# Main.net
KiCad netlist of a schematic drawn in Altium Designer
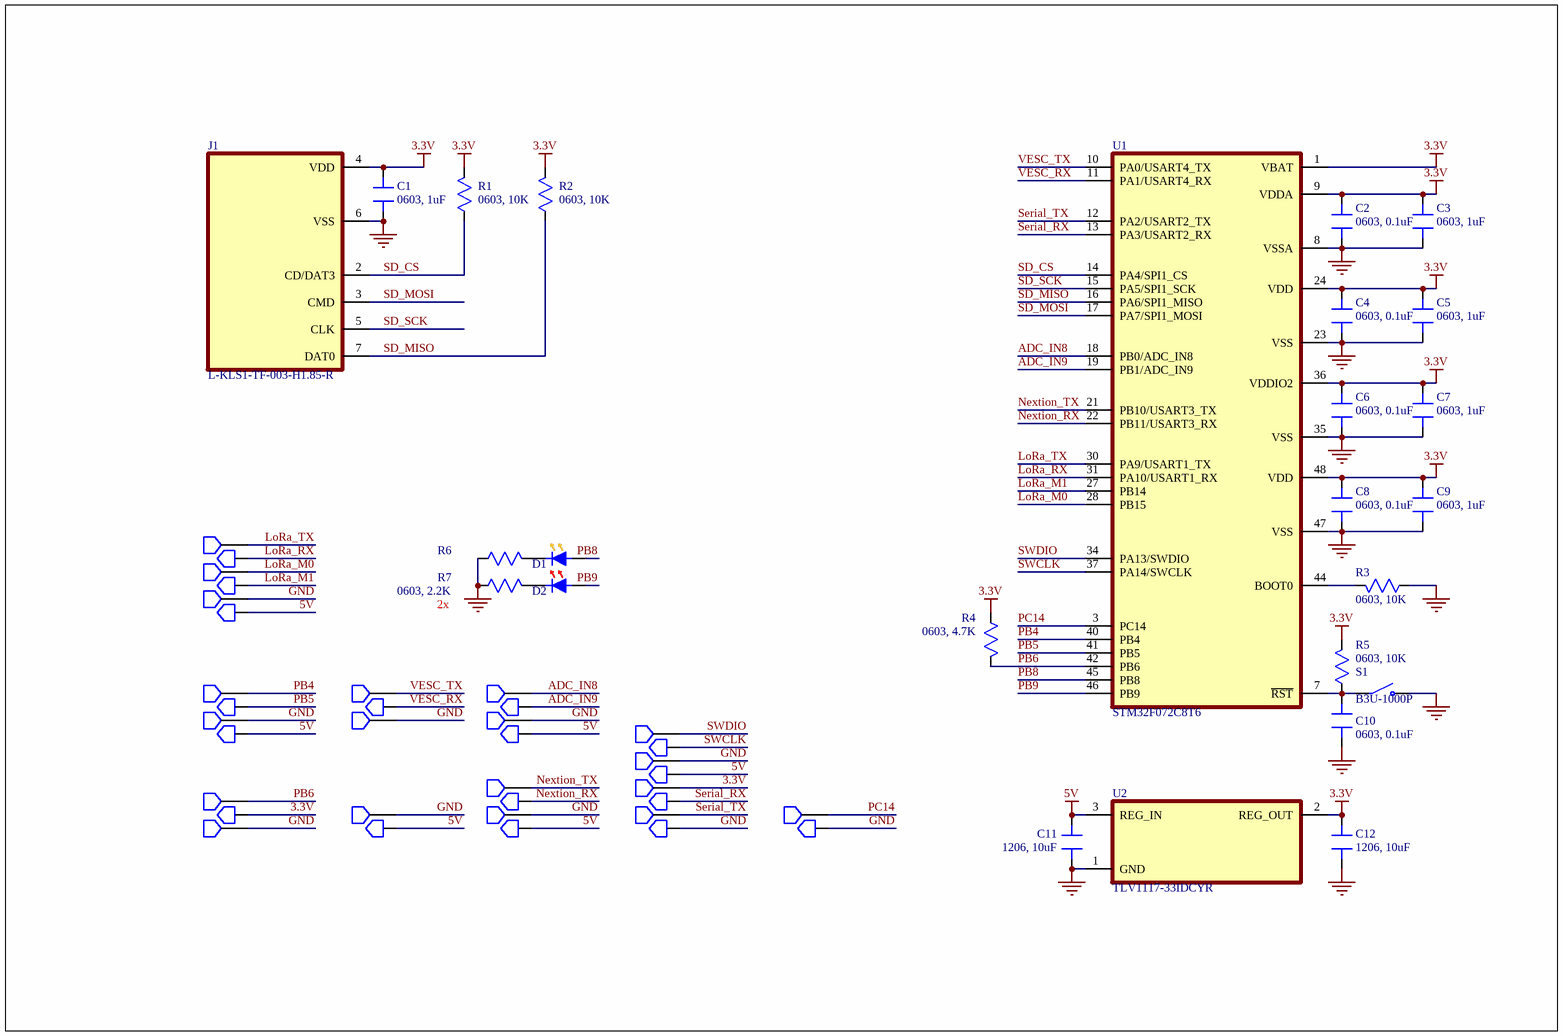
[diagram p0: Main.SchDoc]

(export (version "E")
  (design (tool "Eeschema 10.0.6"))
  (components
    (comp (ref "C1")
      (value "0603, 1uF")
      (footprint "CAP 0603_1608")
      (libsource (lib "Passives") (part "0603 Kapasitör"))
    )
    (comp (ref "C2")
      (value "0603, 0.1uF")
      (footprint "CAP 0603_1608")
      (libsource (lib "Passives") (part "0603 Kapasitör"))
    )
    (comp (ref "C3")
      (value "0603, 1uF")
      (footprint "CAP 0603_1608")
      (libsource (lib "Passives") (part "0603 Kapasitör"))
    )
    (comp (ref "C4")
      (value "0603, 0.1uF")
      (footprint "CAP 0603_1608")
      (libsource (lib "Passives") (part "0603 Kapasitör"))
    )
    (comp (ref "C5")
      (value "0603, 1uF")
      (footprint "CAP 0603_1608")
      (libsource (lib "Passives") (part "0603 Kapasitör"))
    )
    (comp (ref "C6")
      (value "0603, 0.1uF")
      (footprint "CAP 0603_1608")
      (libsource (lib "Passives") (part "0603 Kapasitör"))
    )
    (comp (ref "C7")
      (value "0603, 1uF")
      (footprint "CAP 0603_1608")
      (libsource (lib "Passives") (part "0603 Kapasitör"))
    )
    (comp (ref "C8")
      (value "0603, 0.1uF")
      (footprint "CAP 0603_1608")
      (libsource (lib "Passives") (part "0603 Kapasitör"))
    )
    (comp (ref "C9")
      (value "0603, 1uF")
      (footprint "CAP 0603_1608")
      (libsource (lib "Passives") (part "0603 Kapasitör"))
    )
    (comp (ref "C10")
      (value "0603, 0.1uF")
      (footprint "CAP 0603_1608")
      (libsource (lib "Passives") (part "0603 Kapasitör"))
    )
    (comp (ref "C11")
      (value "1206, 10uF")
      (footprint "CAP 1206_3216")
      (libsource (lib "Passives") (part "1206 Kapasitör"))
    )
    (comp (ref "C12")
      (value "1206, 10uF")
      (footprint "CAP 1206_3216")
      (libsource (lib "Passives") (part "1206 Kapasitör"))
    )
    (comp (ref "D1")
      (value "0805 LED Yellow")
      (footprint "LED 0805_2012 YELLOW")
      (libsource (lib "Passives") (part "0805 LED Yellow"))
    )
    (comp (ref "D2")
      (value "0805 LED Red")
      (footprint "LED 0805_2012 RED")
      (libsource (lib "Passives") (part "0805 LED Red"))
    )
    (comp (ref "J1")
      (value "L-KLS1-TF-003-H1.85-R")
      (footprint "L-KLS1-TF-003-H1.85-R")
      (libsource (lib "L-KLS1-TF-003-H1.85-R") (part "L-KLS1-TF-003-H1.85-R"))
    )
    (comp (ref "P1") (value "Pad1") (footprint "PAD") (libsource (lib "Passives") (part "Pad1")))
    (comp (ref "P2") (value "Pad0") (footprint "PAD") (libsource (lib "Passives") (part "Pad0")))
    (comp (ref "P3") (value "Pad1") (footprint "PAD") (libsource (lib "Passives") (part "Pad1")))
    (comp (ref "P4") (value "Pad0") (footprint "PAD") (libsource (lib "Passives") (part "Pad0")))
    (comp (ref "P5") (value "Pad1") (footprint "PAD") (libsource (lib "Passives") (part "Pad1")))
    (comp (ref "P6") (value "Pad0") (footprint "PAD") (libsource (lib "Passives") (part "Pad0")))
    (comp (ref "P7") (value "Pad1") (footprint "PAD") (libsource (lib "Passives") (part "Pad1")))
    (comp (ref "P8") (value "Pad1") (footprint "PAD") (libsource (lib "Passives") (part "Pad1")))
    (comp (ref "P9") (value "Pad1") (footprint "PAD") (libsource (lib "Passives") (part "Pad1")))
    (comp (ref "P10") (value "Pad0") (footprint "PAD") (libsource (lib "Passives") (part "Pad0")))
    (comp (ref "P11") (value "Pad0") (footprint "PAD") (libsource (lib "Passives") (part "Pad0")))
    (comp (ref "P12") (value "Pad0") (footprint "PAD") (libsource (lib "Passives") (part "Pad0")))
    (comp (ref "P13") (value "Pad1") (footprint "PAD") (libsource (lib "Passives") (part "Pad1")))
    (comp (ref "P14") (value "Pad1") (footprint "PAD") (libsource (lib "Passives") (part "Pad1")))
    (comp (ref "P15") (value "Pad1") (footprint "PAD") (libsource (lib "Passives") (part "Pad1")))
    (comp (ref "P16") (value "Pad0") (footprint "PAD") (libsource (lib "Passives") (part "Pad0")))
    (comp (ref "P17") (value "Pad0") (footprint "PAD") (libsource (lib "Passives") (part "Pad0")))
    (comp (ref "P18") (value "Pad1") (footprint "PAD") (libsource (lib "Passives") (part "Pad1")))
    (comp (ref "P19") (value "Pad0") (footprint "PAD") (libsource (lib "Passives") (part "Pad0")))
    (comp (ref "P20") (value "Pad1") (footprint "PAD") (libsource (lib "Passives") (part "Pad1")))
    (comp (ref "P21") (value "Pad0") (footprint "PAD") (libsource (lib "Passives") (part "Pad0")))
    (comp (ref "P22") (value "Pad1") (footprint "PAD") (libsource (lib "Passives") (part "Pad1")))
    (comp (ref "P23") (value "Pad1") (footprint "PAD") (libsource (lib "Passives") (part "Pad1")))
    (comp (ref "P24") (value "Pad1") (footprint "PAD") (libsource (lib "Passives") (part "Pad1")))
    (comp (ref "P25") (value "Pad0") (footprint "PAD") (libsource (lib "Passives") (part "Pad0")))
    (comp (ref "P26") (value "Pad0") (footprint "PAD") (libsource (lib "Passives") (part "Pad0")))
    (comp (ref "P27") (value "Pad0") (footprint "PAD") (libsource (lib "Passives") (part "Pad0")))
    (comp (ref "P28") (value "Pad1") (footprint "PAD") (libsource (lib "Passives") (part "Pad1")))
    (comp (ref "P29") (value "Pad1") (footprint "PAD") (libsource (lib "Passives") (part "Pad1")))
    (comp (ref "P30") (value "Pad1") (footprint "PAD") (libsource (lib "Passives") (part "Pad1")))
    (comp (ref "P31") (value "Pad1") (footprint "PAD") (libsource (lib "Passives") (part "Pad1")))
    (comp (ref "P32") (value "Pad0") (footprint "PAD") (libsource (lib "Passives") (part "Pad0")))
    (comp (ref "P33") (value "Pad0") (footprint "PAD") (libsource (lib "Passives") (part "Pad0")))
    (comp (ref "P34") (value "Pad0") (footprint "PAD") (libsource (lib "Passives") (part "Pad0")))
    (comp (ref "P35") (value "Pad1") (footprint "PAD") (libsource (lib "Passives") (part "Pad1")))
    (comp (ref "P36") (value "Pad0") (footprint "PAD") (libsource (lib "Passives") (part "Pad0")))
    (comp (ref "R1")
      (value "0603, 10K")
      (footprint "RES 0603_1608")
      (libsource (lib "Passives") (part "0603 Direnç"))
    )
    (comp (ref "R2")
      (value "0603, 10K")
      (footprint "RES 0603_1608")
      (libsource (lib "Passives") (part "0603 Direnç"))
    )
    (comp (ref "R3")
      (value "0603, 10K")
      (footprint "RES 0603_1608")
      (libsource (lib "Passives") (part "0603 Direnç"))
    )
    (comp (ref "R4")
      (value "0603, 4.7K")
      (footprint "RES 0603_1608")
      (libsource (lib "Passives") (part "0603 Direnç"))
    )
    (comp (ref "R5")
      (value "0603, 10K")
      (footprint "RES 0603_1608")
      (libsource (lib "Passives") (part "0603 Direnç"))
    )
    (comp (ref "R6")
      (value "0603, 2.2K")
      (footprint "RES 0603_1608")
      (libsource (lib "Passives") (part "0603 Direnç"))
    )
    (comp (ref "R7")
      (value "0603, 2.2K")
      (footprint "RES 0603_1608")
      (libsource (lib "Passives") (part "0603 Direnç"))
    )
    (comp (ref "S1")
      (value "B3U-1000P")
      (footprint "B3U-1000P")
      (libsource (lib "B3U-1000P") (part "B3U-1000P"))
    )
    (comp (ref "U1")
      (value "STM32F072C8T6")
      (footprint "STM32F072C8T6")
      (libsource (lib "STM32F072C8T6") (part "STM32F072C8T6"))
    )
    (comp (ref "U2")
      (value "TLV1117-33IDCYR")
      (footprint "SOT230P700X180-4N")
      (libsource (lib "TLV1117-33IDCYR") (part "TLV1117-33IDCYR"))
    )
  )
  (nets
    (net (code "1") (name "/ADC_IN8") (class "Default")
      (node (ref "P9") (pin "1") (pinfunction "1_1") (pintype "passive"))
      (node (ref "U1") (pin "18") (pinfunction "PB0/ADC_IN8_18") (pintype "passive"))
    )
    (net (code "2") (name "/ADC_IN9") (class "Default")
      (node (ref "P12") (pin "1") (pinfunction "1_1") (pintype "passive"))
      (node (ref "U1") (pin "19") (pinfunction "PB1/ADC_IN9_19") (pintype "passive"))
    )
    (net (code "3") (name "/LoRa_M0") (class "Default")
      (node (ref "P3") (pin "1") (pinfunction "1_1") (pintype "passive"))
      (node (ref "U1") (pin "28") (pinfunction "PB15_28") (pintype "passive"))
    )
    (net (code "4") (name "/LoRa_M1") (class "Default")
      (node (ref "P4") (pin "1") (pinfunction "1_1") (pintype "passive"))
      (node (ref "U1") (pin "27") (pinfunction "PB14_27") (pintype "passive"))
    )
    (net (code "5") (name "/LoRa_RX") (class "Default")
      (node (ref "P2") (pin "1") (pinfunction "1_1") (pintype "passive"))
      (node (ref "U1") (pin "31") (pinfunction "PA10/USART1_RX_31") (pintype "passive"))
    )
    (net (code "6") (name "/LoRa_TX") (class "Default")
      (node (ref "P1") (pin "1") (pinfunction "1_1") (pintype "passive"))
      (node (ref "U1") (pin "30") (pinfunction "PA9/USART1_TX_30") (pintype "passive"))
    )
    (net (code "7") (name "/Nextion_RX") (class "Default")
      (node (ref "P25") (pin "1") (pinfunction "1_1") (pintype "passive"))
      (node (ref "U1") (pin "22") (pinfunction "PB11/USART3_RX_22") (pintype "passive"))
    )
    (net (code "8") (name "/Nextion_TX") (class "Default")
      (node (ref "P22") (pin "1") (pinfunction "1_1") (pintype "passive"))
      (node (ref "U1") (pin "21") (pinfunction "PB10/USART3_TX_21") (pintype "passive"))
    )
    (net (code "9") (name "/PB4") (class "Default")
      (node (ref "P7") (pin "1") (pinfunction "1_1") (pintype "passive"))
      (node (ref "U1") (pin "40") (pinfunction "PB4_40") (pintype "passive"))
    )
    (net (code "10") (name "/PB5") (class "Default")
      (node (ref "P10") (pin "1") (pinfunction "1_1") (pintype "passive"))
      (node (ref "U1") (pin "41") (pinfunction "PB5_41") (pintype "passive"))
    )
    (net (code "11") (name "/PB6") (class "Default")
      (node (ref "P24") (pin "1") (pinfunction "1_1") (pintype "passive"))
      (node (ref "R4") (pin "2") (pinfunction "2_2") (pintype "passive"))
      (node (ref "U1") (pin "42") (pinfunction "PB6_42") (pintype "passive"))
    )
    (net (code "12") (name "/PB8") (class "Default")
      (node (ref "D1") (pin "1") (pinfunction "1_1") (pintype "passive"))
      (node (ref "U1") (pin "45") (pinfunction "PB8_45") (pintype "passive"))
    )
    (net (code "13") (name "/PB9") (class "Default")
      (node (ref "D2") (pin "1") (pinfunction "1_1") (pintype "passive"))
      (node (ref "U1") (pin "46") (pinfunction "PB9_46") (pintype "passive"))
    )
    (net (code "14") (name "/PC14") (class "Default")
      (node (ref "P35") (pin "1") (pinfunction "1_1") (pintype "passive"))
      (node (ref "U1") (pin "3") (pinfunction "PC14_3") (pintype "passive"))
    )
    (net (code "15") (name "/SD_CS") (class "Default")
      (node (ref "J1") (pin "2") (pinfunction "CD/DAT3_2") (pintype "passive"))
      (node (ref "R1") (pin "2") (pinfunction "2_2") (pintype "passive"))
      (node (ref "U1") (pin "14") (pinfunction "PA4/SPI1_CS_14") (pintype "passive"))
    )
    (net (code "16") (name "/SD_MISO") (class "Default")
      (node (ref "J1") (pin "7") (pinfunction "DAT0_7") (pintype "passive"))
      (node (ref "R2") (pin "2") (pinfunction "2_2") (pintype "passive"))
      (node (ref "U1") (pin "16") (pinfunction "PA6/SPI1_MISO_16") (pintype "passive"))
    )
    (net (code "17") (name "/SD_MOSI") (class "Default")
      (node (ref "J1") (pin "3") (pinfunction "CMD_3") (pintype "passive"))
      (node (ref "U1") (pin "17") (pinfunction "PA7/SPI1_MOSI_17") (pintype "passive"))
    )
    (net (code "18") (name "/SD_SCK") (class "Default")
      (node (ref "J1") (pin "5") (pinfunction "CLK_5") (pintype "passive"))
      (node (ref "U1") (pin "15") (pinfunction "PA5/SPI1_SCK_15") (pintype "passive"))
    )
    (net (code "19") (name "/SWCLK") (class "Default")
      (node (ref "P19") (pin "1") (pinfunction "1_1") (pintype "passive"))
      (node (ref "U1") (pin "37") (pinfunction "PA14/SWCLK_37") (pintype "passive"))
    )
    (net (code "20") (name "/SWDIO") (class "Default")
      (node (ref "P18") (pin "1") (pinfunction "1_1") (pintype "passive"))
      (node (ref "U1") (pin "34") (pinfunction "PA13/SWDIO_34") (pintype "passive"))
    )
    (net (code "21") (name "/Serial_RX") (class "Default")
      (node (ref "P26") (pin "1") (pinfunction "1_1") (pintype "passive"))
      (node (ref "U1") (pin "13") (pinfunction "PA3/USART2_RX_13") (pintype "passive"))
    )
    (net (code "22") (name "/Serial_TX") (class "Default")
      (node (ref "P30") (pin "1") (pinfunction "1_1") (pintype "passive"))
      (node (ref "U1") (pin "12") (pinfunction "PA2/USART2_TX_12") (pintype "passive"))
    )
    (net (code "23") (name "/VESC_RX") (class "Default")
      (node (ref "P11") (pin "1") (pinfunction "1_1") (pintype "passive"))
      (node (ref "U1") (pin "11") (pinfunction "PA1/USART4_RX_11") (pintype "passive"))
    )
    (net (code "24") (name "/VESC_TX") (class "Default")
      (node (ref "P8") (pin "1") (pinfunction "1_1") (pintype "passive"))
      (node (ref "U1") (pin "10") (pinfunction "PA0/USART4_TX_10") (pintype "passive"))
    )
    (net (code "25") (name "3.3V") (class "Default")
      (node (ref "C1") (pin "2") (pinfunction "2_2") (pintype "passive"))
      (node (ref "C12") (pin "2") (pinfunction "2_2") (pintype "passive"))
      (node (ref "C2") (pin "2") (pinfunction "2_2") (pintype "passive"))
      (node (ref "C3") (pin "2") (pinfunction "2_2") (pintype "passive"))
      (node (ref "C4") (pin "2") (pinfunction "2_2") (pintype "passive"))
      (node (ref "C5") (pin "2") (pinfunction "2_2") (pintype "passive"))
      (node (ref "C6") (pin "2") (pinfunction "2_2") (pintype "passive"))
      (node (ref "C7") (pin "2") (pinfunction "2_2") (pintype "passive"))
      (node (ref "C8") (pin "2") (pinfunction "2_2") (pintype "passive"))
      (node (ref "C9") (pin "2") (pinfunction "2_2") (pintype "passive"))
      (node (ref "J1") (pin "4") (pinfunction "VDD_4") (pintype "passive"))
      (node (ref "P23") (pin "1") (pinfunction "1_1") (pintype "passive"))
      (node (ref "P27") (pin "1") (pinfunction "1_1") (pintype "passive"))
      (node (ref "R1") (pin "1") (pinfunction "1_1") (pintype "passive"))
      (node (ref "R2") (pin "1") (pinfunction "1_1") (pintype "passive"))
      (node (ref "R4") (pin "1") (pinfunction "1_1") (pintype "passive"))
      (node (ref "R5") (pin "1") (pinfunction "1_1") (pintype "passive"))
      (node (ref "U1") (pin "1") (pinfunction "VBAT_1") (pintype "passive"))
      (node (ref "U1") (pin "24") (pinfunction "VDD_24") (pintype "passive"))
      (node (ref "U1") (pin "36") (pinfunction "VDDIO2_36") (pintype "passive"))
      (node (ref "U1") (pin "48") (pinfunction "VDD_48") (pintype "passive"))
      (node (ref "U1") (pin "9") (pinfunction "VDDA_9") (pintype "passive"))
      (node (ref "U2") (pin "2") (pinfunction "REG_OUT_2") (pintype "passive"))
    )
    (net (code "26") (name "5V") (class "Default")
      (node (ref "C11") (pin "2") (pinfunction "2_2") (pintype "passive"))
      (node (ref "P16") (pin "1") (pinfunction "1_1") (pintype "passive"))
      (node (ref "P17") (pin "1") (pinfunction "1_1") (pintype "passive"))
      (node (ref "P21") (pin "1") (pinfunction "1_1") (pintype "passive"))
      (node (ref "P32") (pin "1") (pinfunction "1_1") (pintype "passive"))
      (node (ref "P33") (pin "1") (pinfunction "1_1") (pintype "passive"))
      (node (ref "P6") (pin "1") (pinfunction "1_1") (pintype "passive"))
      (node (ref "U2") (pin "3") (pinfunction "REG_IN_3") (pintype "passive"))
    )
    (net (code "27") (name "GND") (class "Default")
      (node (ref "C1") (pin "1") (pinfunction "1_1") (pintype "passive"))
      (node (ref "C10") (pin "1") (pinfunction "1_1") (pintype "passive"))
      (node (ref "C11") (pin "1") (pinfunction "1_1") (pintype "passive"))
      (node (ref "C12") (pin "1") (pinfunction "1_1") (pintype "passive"))
      (node (ref "C2") (pin "1") (pinfunction "1_1") (pintype "passive"))
      (node (ref "C3") (pin "1") (pinfunction "1_1") (pintype "passive"))
      (node (ref "C4") (pin "1") (pinfunction "1_1") (pintype "passive"))
      (node (ref "C5") (pin "1") (pinfunction "1_1") (pintype "passive"))
      (node (ref "C6") (pin "1") (pinfunction "1_1") (pintype "passive"))
      (node (ref "C7") (pin "1") (pinfunction "1_1") (pintype "passive"))
      (node (ref "C8") (pin "1") (pinfunction "1_1") (pintype "passive"))
      (node (ref "C9") (pin "1") (pinfunction "1_1") (pintype "passive"))
      (node (ref "J1") (pin "6") (pinfunction "VSS_6") (pintype "passive"))
      (node (ref "P13") (pin "1") (pinfunction "1_1") (pintype "passive"))
      (node (ref "P14") (pin "1") (pinfunction "1_1") (pintype "passive"))
      (node (ref "P15") (pin "1") (pinfunction "1_1") (pintype "passive"))
      (node (ref "P20") (pin "1") (pinfunction "1_1") (pintype "passive"))
      (node (ref "P28") (pin "1") (pinfunction "1_1") (pintype "passive"))
      (node (ref "P29") (pin "1") (pinfunction "1_1") (pintype "passive"))
      (node (ref "P31") (pin "1") (pinfunction "1_1") (pintype "passive"))
      (node (ref "P34") (pin "1") (pinfunction "1_1") (pintype "passive"))
      (node (ref "P36") (pin "1") (pinfunction "1_1") (pintype "passive"))
      (node (ref "P5") (pin "1") (pinfunction "1_1") (pintype "passive"))
      (node (ref "R3") (pin "2") (pinfunction "2_2") (pintype "passive"))
      (node (ref "R6") (pin "1") (pinfunction "1_1") (pintype "passive"))
      (node (ref "R7") (pin "1") (pinfunction "1_1") (pintype "passive"))
      (node (ref "S1") (pin "2") (pinfunction "2_2") (pintype "passive"))
      (node (ref "U1") (pin "23") (pinfunction "VSS_23") (pintype "passive"))
      (node (ref "U1") (pin "35") (pinfunction "VSS_35") (pintype "passive"))
      (node (ref "U1") (pin "47") (pinfunction "VSS_47") (pintype "passive"))
      (node (ref "U1") (pin "8") (pinfunction "VSSA_8") (pintype "passive"))
      (node (ref "U2") (pin "1") (pinfunction "GND_1") (pintype "passive"))
    )
    (net (code "28") (name "Net-(D1-Pad2)") (class "Default")
      (node (ref "D1") (pin "2") (pinfunction "2_2") (pintype "passive"))
      (node (ref "R6") (pin "2") (pinfunction "2_2") (pintype "passive"))
    )
    (net (code "29") (name "Net-(D2-Pad2)") (class "Default")
      (node (ref "D2") (pin "2") (pinfunction "2_2") (pintype "passive"))
      (node (ref "R7") (pin "2") (pinfunction "2_2") (pintype "passive"))
    )
    (net (code "30") (name "Net-(U1-BOOT0)") (class "Default")
      (node (ref "R3") (pin "1") (pinfunction "1_1") (pintype "passive"))
      (node (ref "U1") (pin "44") (pinfunction "BOOT0_44") (pintype "passive"))
    )
    (net (code "31") (name "Net-(U1-~{RST})") (class "Default")
      (node (ref "C10") (pin "2") (pinfunction "2_2") (pintype "passive"))
      (node (ref "R5") (pin "2") (pinfunction "2_2") (pintype "passive"))
      (node (ref "S1") (pin "1") (pinfunction "1_1") (pintype "passive"))
      (node (ref "U1") (pin "7") (pinfunction "~{RST}_7") (pintype "passive"))
    )
  )
)
